# relay-shield.net
KiCad netlist of a schematic drawn in EAGLE
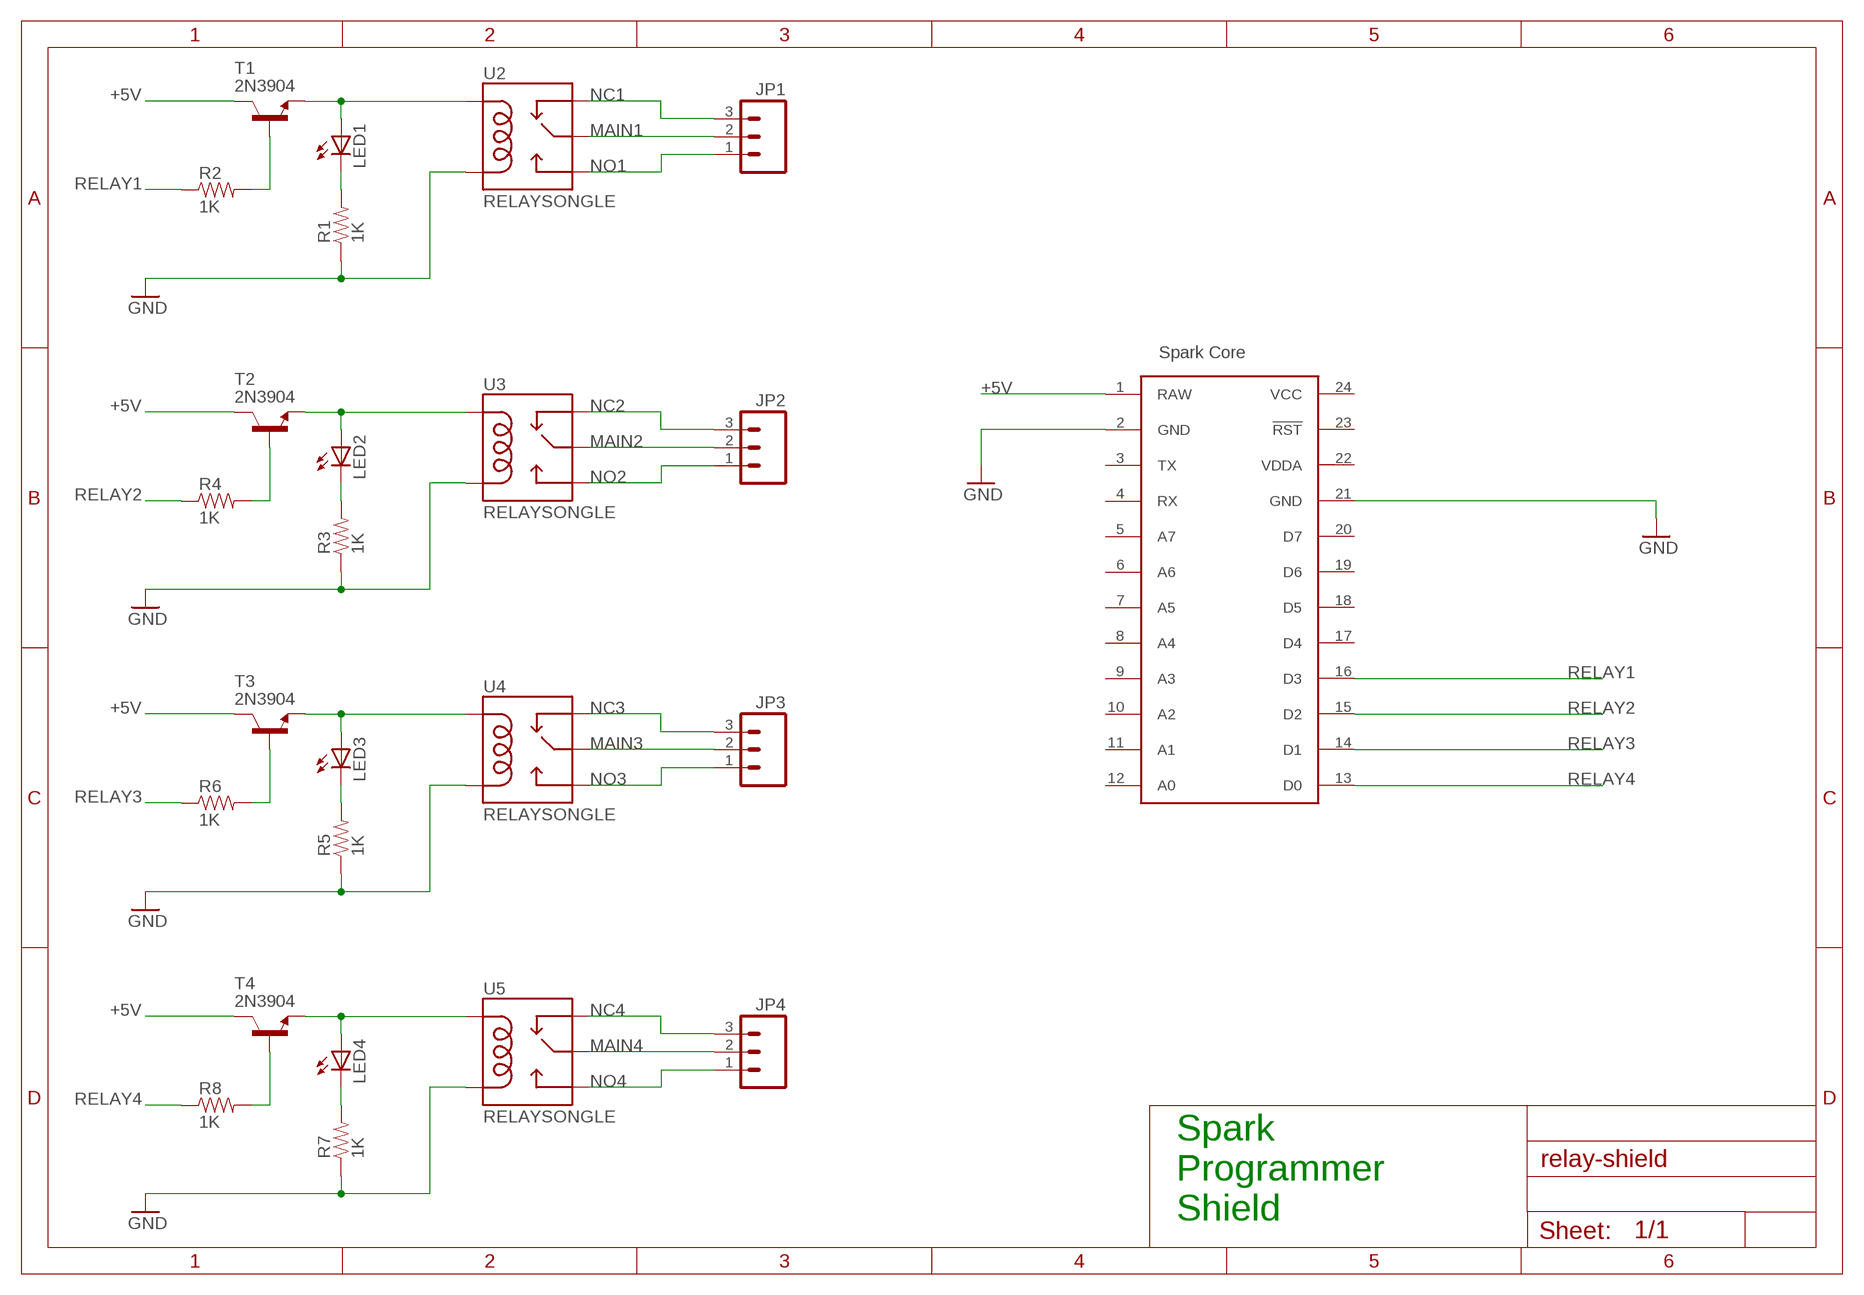
[diagram p0: schematic, sheet 1]

(export (version "E")
  (design (tool "Eeschema 10.0.6"))
  (components
    (comp (ref "JP1")
      (value "M03-SCREW-5MM")
      (footprint "eagle-import:SCREWTERMINAL-5MM-3")
      (libsource (lib "eagle-import") (part "M03-SCREW-5MM"))
    )
    (comp (ref "JP2")
      (value "M03-SCREW-5MM")
      (footprint "eagle-import:SCREWTERMINAL-5MM-3")
      (libsource (lib "eagle-import") (part "M03-SCREW-5MM"))
    )
    (comp (ref "JP3")
      (value "M03-SCREW-5MM")
      (footprint "eagle-import:SCREWTERMINAL-5MM-3")
      (libsource (lib "eagle-import") (part "M03-SCREW-5MM"))
    )
    (comp (ref "JP4")
      (value "M03-SCREW-5MM")
      (footprint "eagle-import:SCREWTERMINAL-5MM-3")
      (libsource (lib "eagle-import") (part "M03-SCREW-5MM"))
    )
    (comp (ref "LED1")
      (value "LED3MM")
      (footprint "eagle-import:LED3MM")
      (libsource (lib "eagle-import") (part "LED3MM"))
    )
    (comp (ref "LED2")
      (value "LED3MM")
      (footprint "eagle-import:LED3MM")
      (libsource (lib "eagle-import") (part "LED3MM"))
    )
    (comp (ref "LED3")
      (value "LED3MM")
      (footprint "eagle-import:LED3MM")
      (libsource (lib "eagle-import") (part "LED3MM"))
    )
    (comp (ref "LED4")
      (value "LED3MM")
      (footprint "eagle-import:LED3MM")
      (libsource (lib "eagle-import") (part "LED3MM"))
    )
    (comp (ref "R1")
      (value "1K")
      (footprint "eagle-import:AXIAL-0.3")
      (libsource (lib "eagle-import") (part "RESISTORAXIAL-0.3"))
    )
    (comp (ref "R2")
      (value "1K")
      (footprint "eagle-import:AXIAL-0.3")
      (libsource (lib "eagle-import") (part "RESISTORAXIAL-0.3"))
    )
    (comp (ref "R3")
      (value "1K")
      (footprint "eagle-import:AXIAL-0.3")
      (libsource (lib "eagle-import") (part "RESISTORAXIAL-0.3"))
    )
    (comp (ref "R4")
      (value "1K")
      (footprint "eagle-import:AXIAL-0.3")
      (libsource (lib "eagle-import") (part "RESISTORAXIAL-0.3"))
    )
    (comp (ref "R5")
      (value "1K")
      (footprint "eagle-import:AXIAL-0.3")
      (libsource (lib "eagle-import") (part "RESISTORAXIAL-0.3"))
    )
    (comp (ref "R6")
      (value "1K")
      (footprint "eagle-import:AXIAL-0.3")
      (libsource (lib "eagle-import") (part "RESISTORAXIAL-0.3"))
    )
    (comp (ref "R7")
      (value "1K")
      (footprint "eagle-import:AXIAL-0.3")
      (libsource (lib "eagle-import") (part "RESISTORAXIAL-0.3"))
    )
    (comp (ref "R8")
      (value "1K")
      (footprint "eagle-import:AXIAL-0.3")
      (libsource (lib "eagle-import") (part "RESISTORAXIAL-0.3"))
    )
    (comp (ref "T1")
      (value "2N3904")
      (footprint "eagle-import:TO92")
      (libsource (lib "eagle-import") (part "2N3904"))
    )
    (comp (ref "T2")
      (value "2N3904")
      (footprint "eagle-import:TO92")
      (libsource (lib "eagle-import") (part "2N3904"))
    )
    (comp (ref "T3")
      (value "2N3904")
      (footprint "eagle-import:TO92")
      (libsource (lib "eagle-import") (part "2N3904"))
    )
    (comp (ref "T4")
      (value "2N3904")
      (footprint "eagle-import:TO92")
      (libsource (lib "eagle-import") (part "2N3904"))
    )
    (comp (ref "U1")
      (value "SPARK_CORECORE")
      (footprint "eagle-import:SPARK_CORE")
      (libsource (lib "eagle-import") (part "SPARK_CORECORE"))
    )
    (comp (ref "U2")
      (value "RELAYSONGLE")
      (footprint "eagle-import:SRD-5VDC-SL-C")
      (libsource (lib "eagle-import") (part "RELAYSONGLE"))
    )
    (comp (ref "U3")
      (value "RELAYSONGLE")
      (footprint "eagle-import:SRD-5VDC-SL-C")
      (libsource (lib "eagle-import") (part "RELAYSONGLE"))
    )
    (comp (ref "U4")
      (value "RELAYSONGLE")
      (footprint "eagle-import:SRD-5VDC-SL-C")
      (libsource (lib "eagle-import") (part "RELAYSONGLE"))
    )
    (comp (ref "U5")
      (value "RELAYSONGLE")
      (footprint "eagle-import:SRD-5VDC-SL-C")
      (libsource (lib "eagle-import") (part "RELAYSONGLE"))
    )
  )
  (nets
    (net (code "1") (name "/+5V") (class "Default")
      (node (ref "T1") (pin "1") (pinfunction "C_1") (pintype "passive"))
      (node (ref "T2") (pin "1") (pinfunction "C_1") (pintype "passive"))
      (node (ref "T3") (pin "1") (pinfunction "C_1") (pintype "passive"))
      (node (ref "T4") (pin "1") (pinfunction "C_1") (pintype "passive"))
      (node (ref "U1") (pin "1") (pinfunction "RAW_1") (pintype "power_in"))
    )
    (net (code "2") (name "/MAIN1") (class "Default")
      (node (ref "JP1") (pin "2") (pinfunction "2_2") (pintype "passive"))
      (node (ref "U2") (pin "COMMON") (pinfunction "MAIN_COMMON") (pintype "bidirectional"))
    )
    (net (code "3") (name "/MAIN2") (class "Default")
      (node (ref "JP2") (pin "2") (pinfunction "2_2") (pintype "passive"))
      (node (ref "U3") (pin "COMMON") (pinfunction "MAIN_COMMON") (pintype "bidirectional"))
    )
    (net (code "4") (name "/MAIN3") (class "Default")
      (node (ref "JP3") (pin "2") (pinfunction "2_2") (pintype "passive"))
      (node (ref "U4") (pin "COMMON") (pinfunction "MAIN_COMMON") (pintype "bidirectional"))
    )
    (net (code "5") (name "/MAIN4") (class "Default")
      (node (ref "JP4") (pin "2") (pinfunction "2_2") (pintype "passive"))
      (node (ref "U5") (pin "COMMON") (pinfunction "MAIN_COMMON") (pintype "bidirectional"))
    )
    (net (code "6") (name "/NC1") (class "Default")
      (node (ref "JP1") (pin "3") (pinfunction "3_3") (pintype "passive"))
      (node (ref "U2") (pin "CLOSED") (pinfunction "NC_CLOSED") (pintype "bidirectional"))
    )
    (net (code "7") (name "/NC2") (class "Default")
      (node (ref "JP2") (pin "3") (pinfunction "3_3") (pintype "passive"))
      (node (ref "U3") (pin "CLOSED") (pinfunction "NC_CLOSED") (pintype "bidirectional"))
    )
    (net (code "8") (name "/NC3") (class "Default")
      (node (ref "JP3") (pin "3") (pinfunction "3_3") (pintype "passive"))
      (node (ref "U4") (pin "CLOSED") (pinfunction "NC_CLOSED") (pintype "bidirectional"))
    )
    (net (code "9") (name "/NC4") (class "Default")
      (node (ref "JP4") (pin "3") (pinfunction "3_3") (pintype "passive"))
      (node (ref "U5") (pin "CLOSED") (pinfunction "NC_CLOSED") (pintype "bidirectional"))
    )
    (net (code "10") (name "/NO1") (class "Default")
      (node (ref "JP1") (pin "1") (pinfunction "1_1") (pintype "passive"))
      (node (ref "U2") (pin "OPEN") (pinfunction "NO_OPEN") (pintype "bidirectional"))
    )
    (net (code "11") (name "/NO2") (class "Default")
      (node (ref "JP2") (pin "1") (pinfunction "1_1") (pintype "passive"))
      (node (ref "U3") (pin "OPEN") (pinfunction "NO_OPEN") (pintype "bidirectional"))
    )
    (net (code "12") (name "/NO3") (class "Default")
      (node (ref "JP3") (pin "1") (pinfunction "1_1") (pintype "passive"))
      (node (ref "U4") (pin "OPEN") (pinfunction "NO_OPEN") (pintype "bidirectional"))
    )
    (net (code "13") (name "/NO4") (class "Default")
      (node (ref "JP4") (pin "1") (pinfunction "1_1") (pintype "passive"))
      (node (ref "U5") (pin "OPEN") (pinfunction "NO_OPEN") (pintype "bidirectional"))
    )
    (net (code "14") (name "/RELAY1") (class "Default")
      (node (ref "R2") (pin "P$1") (pinfunction "1_P$1") (pintype "passive"))
      (node (ref "U1") (pin "16") (pinfunction "D3_16") (pintype "bidirectional"))
    )
    (net (code "15") (name "/RELAY2") (class "Default")
      (node (ref "R4") (pin "P$1") (pinfunction "1_P$1") (pintype "passive"))
      (node (ref "U1") (pin "15") (pinfunction "D2_15") (pintype "bidirectional"))
    )
    (net (code "16") (name "/RELAY3") (class "Default")
      (node (ref "R6") (pin "P$1") (pinfunction "1_P$1") (pintype "passive"))
      (node (ref "U1") (pin "14") (pinfunction "D1_14") (pintype "bidirectional"))
    )
    (net (code "17") (name "/RELAY4") (class "Default")
      (node (ref "R8") (pin "P$1") (pinfunction "1_P$1") (pintype "passive"))
      (node (ref "U1") (pin "13") (pinfunction "D0_13") (pintype "bidirectional"))
    )
    (net (code "18") (name "/VCC") (class "Default")
      (node (ref "U1") (pin "24") (pinfunction "VCC_24") (pintype "power_in"))
    )
    (net (code "19") (name "/VDDA") (class "Default")
      (node (ref "U1") (pin "22") (pinfunction "VDDA_22") (pintype "power_in"))
    )
    (net (code "20") (name "GND") (class "Default")
      (node (ref "R1") (pin "P$1") (pinfunction "1_P$1") (pintype "passive"))
      (node (ref "R3") (pin "P$1") (pinfunction "1_P$1") (pintype "passive"))
      (node (ref "R5") (pin "P$1") (pinfunction "1_P$1") (pintype "passive"))
      (node (ref "R7") (pin "P$1") (pinfunction "1_P$1") (pintype "passive"))
      (node (ref "U1") (pin "2") (pinfunction "GND_2") (pintype "power_in"))
      (node (ref "U1") (pin "21") (pinfunction "GND_21") (pintype "power_in"))
      (node (ref "U2") (pin "COIL2") (pinfunction "COIL2_COIL2") (pintype "bidirectional"))
      (node (ref "U3") (pin "COIL2") (pinfunction "COIL2_COIL2") (pintype "bidirectional"))
      (node (ref "U4") (pin "COIL2") (pinfunction "COIL2_COIL2") (pintype "bidirectional"))
      (node (ref "U5") (pin "COIL2") (pinfunction "COIL2_COIL2") (pintype "bidirectional"))
    )
    (net (code "21") (name "Net-(LED1-C)") (class "Default")
      (node (ref "LED1") (pin "K") (pinfunction "C_K") (pintype "passive"))
      (node (ref "R1") (pin "P$2") (pinfunction "2_P$2") (pintype "passive"))
    )
    (net (code "22") (name "Net-(LED2-C)") (class "Default")
      (node (ref "LED2") (pin "K") (pinfunction "C_K") (pintype "passive"))
      (node (ref "R3") (pin "P$2") (pinfunction "2_P$2") (pintype "passive"))
    )
    (net (code "23") (name "Net-(LED3-C)") (class "Default")
      (node (ref "LED3") (pin "K") (pinfunction "C_K") (pintype "passive"))
      (node (ref "R5") (pin "P$2") (pinfunction "2_P$2") (pintype "passive"))
    )
    (net (code "24") (name "Net-(LED4-C)") (class "Default")
      (node (ref "LED4") (pin "K") (pinfunction "C_K") (pintype "passive"))
      (node (ref "R7") (pin "P$2") (pinfunction "2_P$2") (pintype "passive"))
    )
    (net (code "25") (name "Net-(R2-2)") (class "Default")
      (node (ref "R2") (pin "P$2") (pinfunction "2_P$2") (pintype "passive"))
      (node (ref "T1") (pin "2") (pinfunction "B_2") (pintype "passive"))
    )
    (net (code "26") (name "Net-(R4-2)") (class "Default")
      (node (ref "R4") (pin "P$2") (pinfunction "2_P$2") (pintype "passive"))
      (node (ref "T2") (pin "2") (pinfunction "B_2") (pintype "passive"))
    )
    (net (code "27") (name "Net-(R6-2)") (class "Default")
      (node (ref "R6") (pin "P$2") (pinfunction "2_P$2") (pintype "passive"))
      (node (ref "T3") (pin "2") (pinfunction "B_2") (pintype "passive"))
    )
    (net (code "28") (name "Net-(R8-2)") (class "Default")
      (node (ref "R8") (pin "P$2") (pinfunction "2_P$2") (pintype "passive"))
      (node (ref "T4") (pin "2") (pinfunction "B_2") (pintype "passive"))
    )
    (net (code "29") (name "Net-(T1-E)") (class "Default")
      (node (ref "LED1") (pin "A") (pinfunction "A_A") (pintype "passive"))
      (node (ref "T1") (pin "3") (pinfunction "E_3") (pintype "passive"))
      (node (ref "U2") (pin "COIL1") (pinfunction "COIL1_COIL1") (pintype "bidirectional"))
    )
    (net (code "30") (name "Net-(T2-E)") (class "Default")
      (node (ref "LED2") (pin "A") (pinfunction "A_A") (pintype "passive"))
      (node (ref "T2") (pin "3") (pinfunction "E_3") (pintype "passive"))
      (node (ref "U3") (pin "COIL1") (pinfunction "COIL1_COIL1") (pintype "bidirectional"))
    )
    (net (code "31") (name "Net-(T3-E)") (class "Default")
      (node (ref "LED3") (pin "A") (pinfunction "A_A") (pintype "passive"))
      (node (ref "T3") (pin "3") (pinfunction "E_3") (pintype "passive"))
      (node (ref "U4") (pin "COIL1") (pinfunction "COIL1_COIL1") (pintype "bidirectional"))
    )
    (net (code "32") (name "Net-(T4-E)") (class "Default")
      (node (ref "LED4") (pin "A") (pinfunction "A_A") (pintype "passive"))
      (node (ref "T4") (pin "3") (pinfunction "E_3") (pintype "passive"))
      (node (ref "U5") (pin "COIL1") (pinfunction "COIL1_COIL1") (pintype "bidirectional"))
    )
    (net (code "33") (name "unconnected-(U1-A0-Pad12)") (class "Default")
      (node (ref "U1") (pin "12") (pinfunction "A0_12") (pintype "bidirectional"))
    )
    (net (code "34") (name "unconnected-(U1-A1-Pad11)") (class "Default")
      (node (ref "U1") (pin "11") (pinfunction "A1_11") (pintype "bidirectional"))
    )
    (net (code "35") (name "unconnected-(U1-A2-Pad10)") (class "Default")
      (node (ref "U1") (pin "10") (pinfunction "A2_10") (pintype "bidirectional"))
    )
    (net (code "36") (name "unconnected-(U1-A3-Pad9)") (class "Default")
      (node (ref "U1") (pin "9") (pinfunction "A3_9") (pintype "bidirectional"))
    )
    (net (code "37") (name "unconnected-(U1-A4-Pad8)") (class "Default")
      (node (ref "U1") (pin "8") (pinfunction "A4_8") (pintype "bidirectional"))
    )
    (net (code "38") (name "unconnected-(U1-A5-Pad7)") (class "Default")
      (node (ref "U1") (pin "7") (pinfunction "A5_7") (pintype "bidirectional"))
    )
    (net (code "39") (name "unconnected-(U1-A6-Pad6)") (class "Default")
      (node (ref "U1") (pin "6") (pinfunction "A6_6") (pintype "bidirectional"))
    )
    (net (code "40") (name "unconnected-(U1-A7-Pad5)") (class "Default")
      (node (ref "U1") (pin "5") (pinfunction "A7_5") (pintype "bidirectional"))
    )
    (net (code "41") (name "unconnected-(U1-D4-Pad17)") (class "Default")
      (node (ref "U1") (pin "17") (pinfunction "D4_17") (pintype "bidirectional"))
    )
    (net (code "42") (name "unconnected-(U1-D5-Pad18)") (class "Default")
      (node (ref "U1") (pin "18") (pinfunction "D5_18") (pintype "bidirectional"))
    )
    (net (code "43") (name "unconnected-(U1-D6-Pad19)") (class "Default")
      (node (ref "U1") (pin "19") (pinfunction "D6_19") (pintype "bidirectional"))
    )
    (net (code "44") (name "unconnected-(U1-D7-Pad20)") (class "Default")
      (node (ref "U1") (pin "20") (pinfunction "D7_20") (pintype "bidirectional"))
    )
    (net (code "45") (name "unconnected-(U1-RX-Pad4)") (class "Default")
      (node (ref "U1") (pin "4") (pinfunction "RX_4") (pintype "bidirectional"))
    )
    (net (code "46") (name "unconnected-(U1-TX-Pad3)") (class "Default")
      (node (ref "U1") (pin "3") (pinfunction "TX_3") (pintype "bidirectional"))
    )
    (net (code "47") (name "unconnected-(U1-~{RST}-Pad23)") (class "Default")
      (node (ref "U1") (pin "23") (pinfunction "~{RST}_23") (pintype "bidirectional"))
    )
  )
)
